# design.net
KiCad netlist of a schematic drawn in EasyEDA
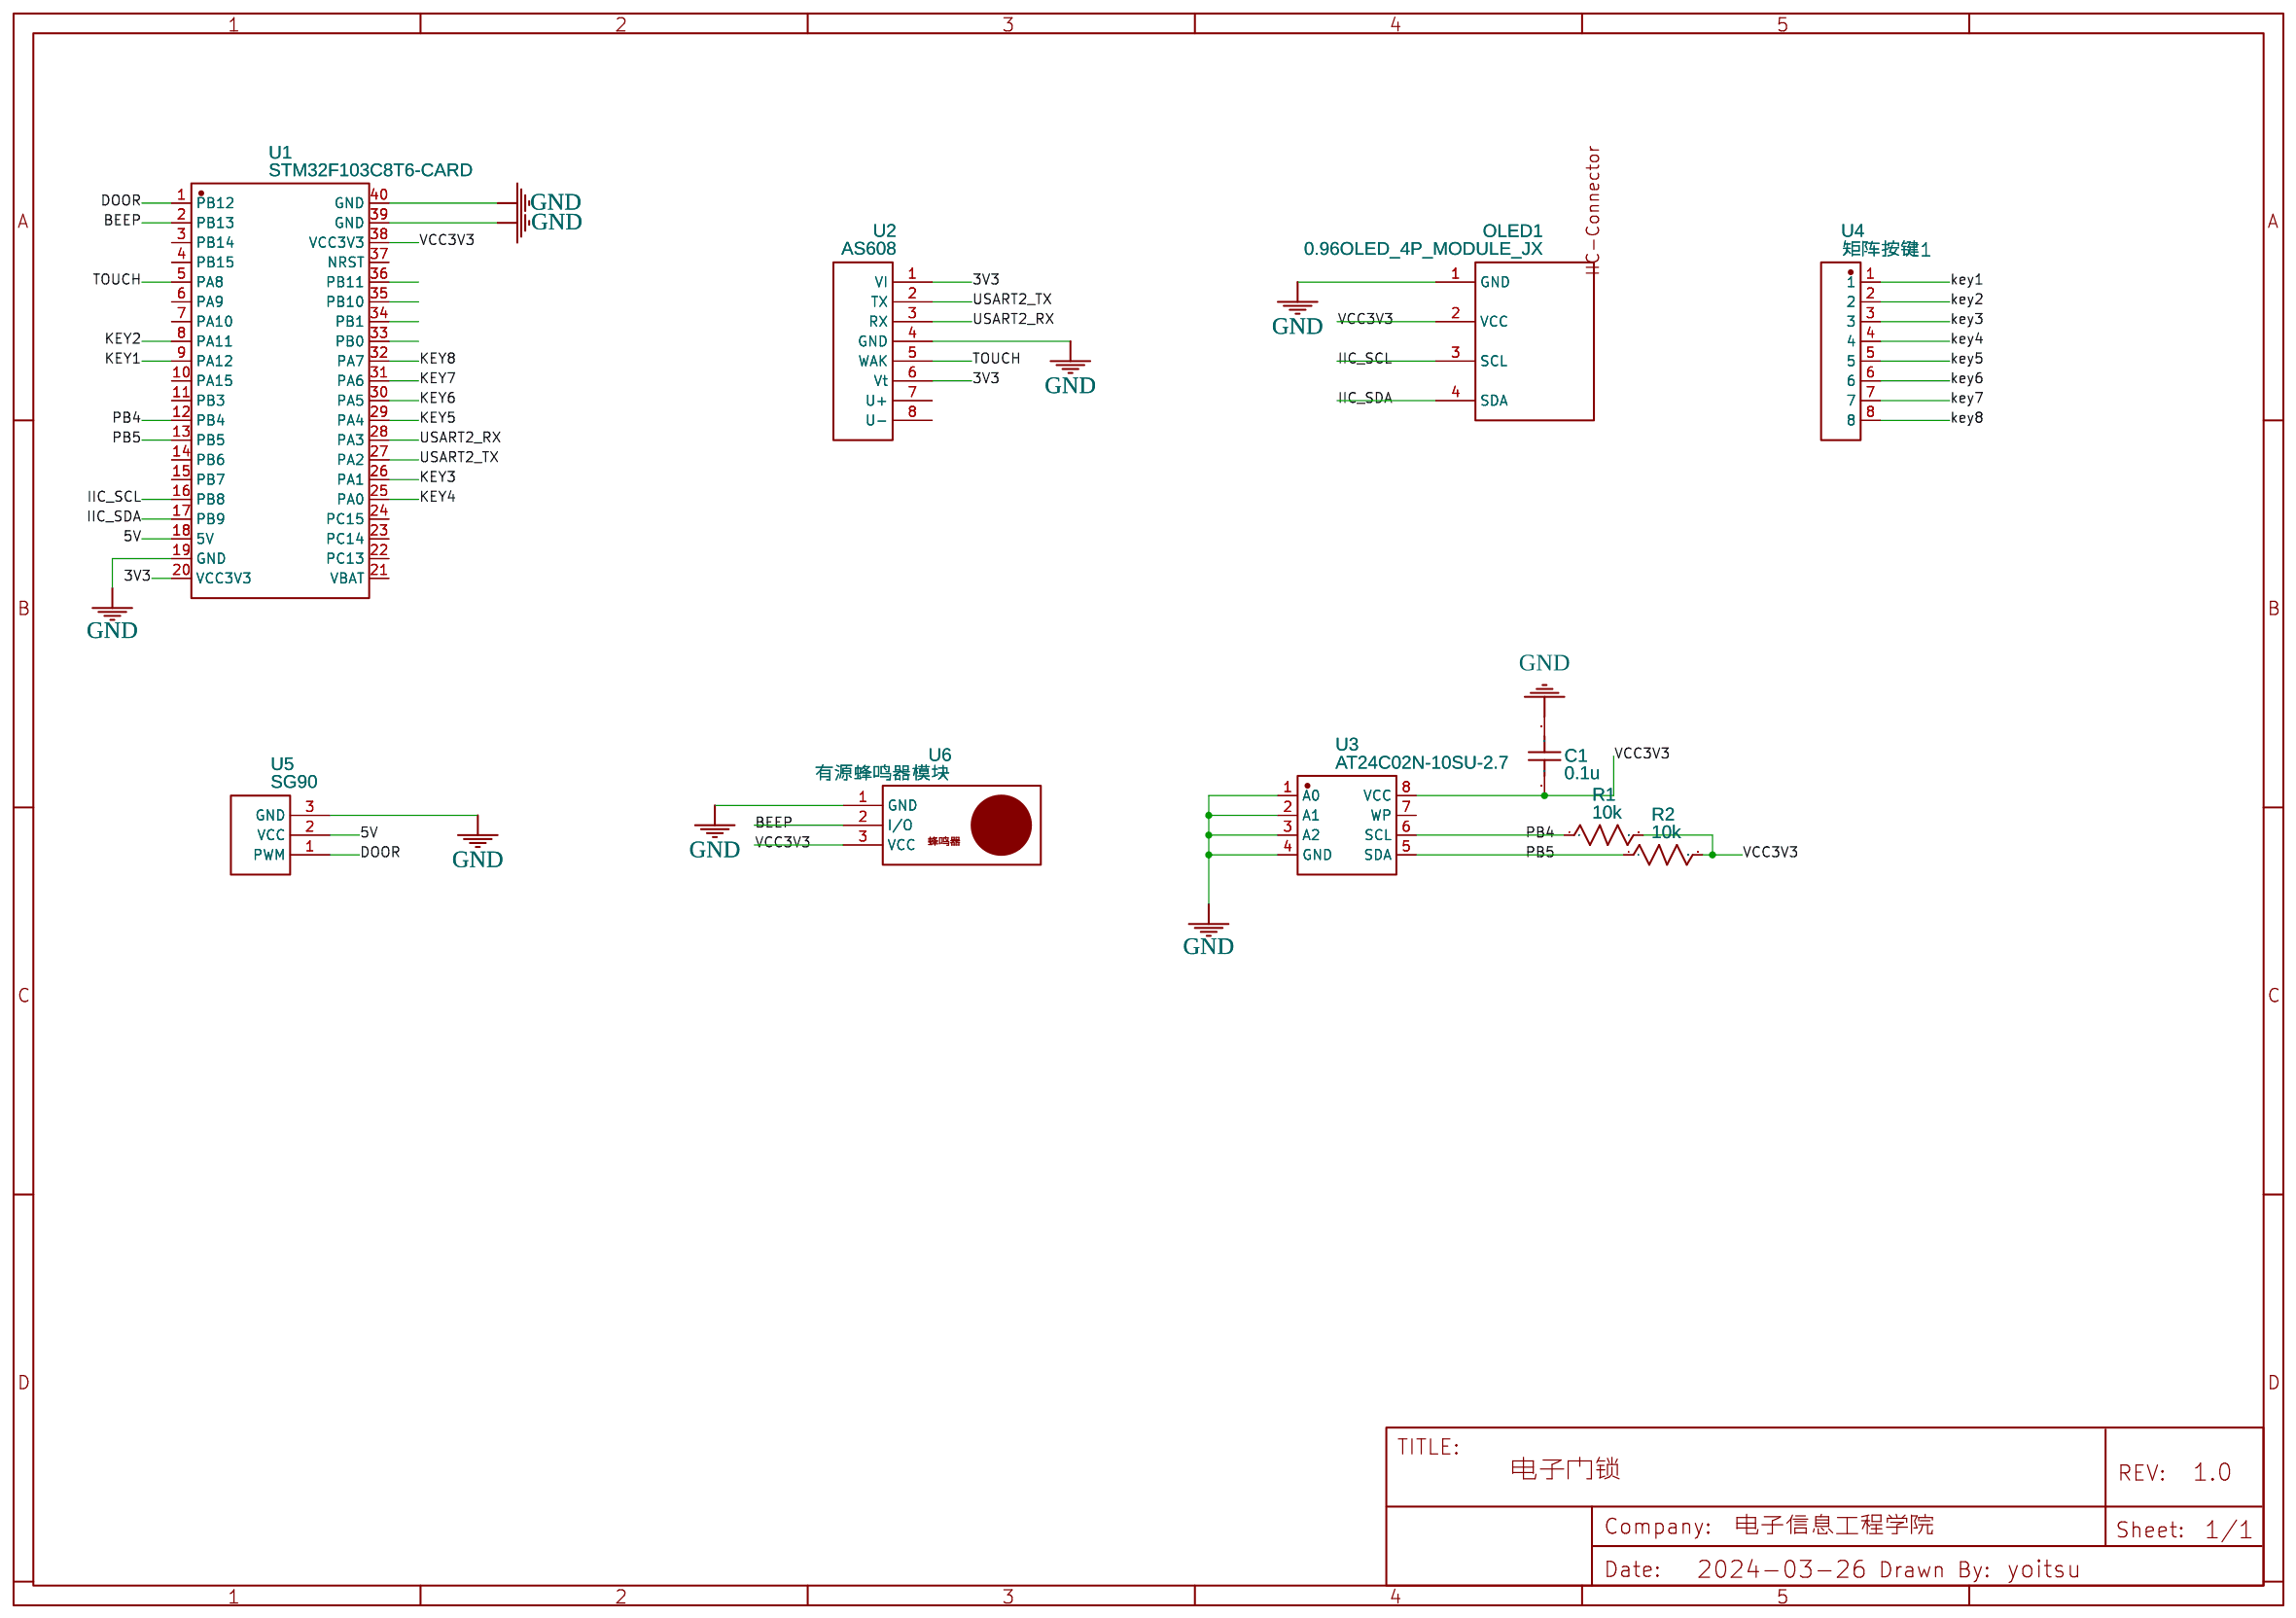
[diagram p0: schematic sheet]

(export (version "E")
  (design (tool "Eeschema 10.0.6"))
  (components
    (comp (ref "C1") (value "0.1u") (libsource (lib "") (part "C_0603_US")))
    (comp (ref "OLED1") (value "0.96OLED_4P_MODULE_JX") (libsource (lib "") (part "0.96OLED_4P_MODULE_JX")))
    (comp (ref "R1") (value "10k") (libsource (lib "") (part "R_0805_US")))
    (comp (ref "R2") (value "10k") (libsource (lib "") (part "R_0805_US")))
    (comp (ref "U1")
      (value "STM32F103C8T6-CARD")
      (fields (field (name "Manufacturer Part") "STM32F103C8T6-Card"))
      (libsource (lib "") (part "STM32F103C8T6-CARD"))
    )
    (comp (ref "U2")
      (value "AS608")
      (fields (field (name "Manufacturer") "lengyuefeng") (field (name "Supplier") "lengyuefeng"))
      (libsource (lib "") (part "AS608"))
    )
    (comp (ref "U3") (value "AT24C02N-10SU-2.7") (libsource (lib "") (part "AT24C02N-10SU-2.7")))
    (comp (ref "U4")
      (value "矩阵按键1")
      (fields
        (field (name "Manufacturer Part") "KH-2.54FH-1X8P-H8.5")
        (field (name "Manufacturer") "kinghelm(金航标)")
      )
      (libsource (lib "") (part "KH-2.54FH-1X8P-H8.5"))
    )
    (comp (ref "U5") (value "SG90") (libsource (lib "") (part "SG90")))
    (comp (ref "U6") (value "有源蜂鸣器模块") (libsource (lib "") (part "有源蜂鸣器模块")))
  )
  (nets
    (net (code "1") (name "/3V3") (class "Default")
      (node (ref "U1") (pin "20") (pinfunction "VCC3V3_20") (pintype "unspecified"))
      (node (ref "U2") (pin "1") (pinfunction "VI_1") (pintype "unspecified"))
      (node (ref "U2") (pin "6") (pinfunction "Vt_6") (pintype "unspecified"))
    )
    (net (code "2") (name "/5V") (class "Default")
      (node (ref "U1") (pin "18") (pinfunction "5V_18") (pintype "unspecified"))
      (node (ref "U5") (pin "2") (pinfunction "VCC_2") (pintype "unspecified"))
    )
    (net (code "3") (name "/BEEP") (class "Default")
      (node (ref "U1") (pin "2") (pinfunction "PB13_2") (pintype "unspecified"))
      (node (ref "U6") (pin "2") (pinfunction "I/O_2") (pintype "unspecified"))
    )
    (net (code "4") (name "/DOOR") (class "Default")
      (node (ref "U1") (pin "1") (pinfunction "PB12_1") (pintype "unspecified"))
      (node (ref "U5") (pin "1") (pinfunction "PWM_1") (pintype "unspecified"))
    )
    (net (code "5") (name "/IIC_SCL") (class "Default")
      (node (ref "OLED1") (pin "3") (pinfunction "SCL_3") (pintype "unspecified"))
      (node (ref "U1") (pin "16") (pinfunction "PB8_16") (pintype "unspecified"))
    )
    (net (code "6") (name "/IIC_SDA") (class "Default")
      (node (ref "OLED1") (pin "4") (pinfunction "SDA_4") (pintype "unspecified"))
      (node (ref "U1") (pin "17") (pinfunction "PB9_17") (pintype "unspecified"))
    )
    (net (code "7") (name "/KEY1") (class "Default")
      (node (ref "U1") (pin "9") (pinfunction "PA12_9") (pintype "unspecified"))
    )
    (net (code "8") (name "/KEY2") (class "Default")
      (node (ref "U1") (pin "8") (pinfunction "PA11_8") (pintype "unspecified"))
    )
    (net (code "9") (name "/KEY3") (class "Default")
      (node (ref "U1") (pin "26") (pinfunction "PA1_26") (pintype "unspecified"))
    )
    (net (code "10") (name "/KEY4") (class "Default")
      (node (ref "U1") (pin "25") (pinfunction "PA0_25") (pintype "unspecified"))
    )
    (net (code "11") (name "/KEY5") (class "Default")
      (node (ref "U1") (pin "29") (pinfunction "PA4_29") (pintype "unspecified"))
    )
    (net (code "12") (name "/KEY6") (class "Default")
      (node (ref "U1") (pin "30") (pinfunction "PA5_30") (pintype "unspecified"))
    )
    (net (code "13") (name "/KEY7") (class "Default")
      (node (ref "U1") (pin "31") (pinfunction "PA6_31") (pintype "unspecified"))
    )
    (net (code "14") (name "/KEY8") (class "Default")
      (node (ref "U1") (pin "32") (pinfunction "PA7_32") (pintype "unspecified"))
    )
    (net (code "15") (name "/PB4") (class "Default")
      (node (ref "R1") (pin "1") (pinfunction "1_1") (pintype "unspecified"))
      (node (ref "U1") (pin "12") (pinfunction "PB4_12") (pintype "unspecified"))
      (node (ref "U3") (pin "6") (pinfunction "SCL_6") (pintype "unspecified"))
    )
    (net (code "16") (name "/PB5") (class "Default")
      (node (ref "R2") (pin "1") (pinfunction "1_1") (pintype "unspecified"))
      (node (ref "U1") (pin "13") (pinfunction "PB5_13") (pintype "unspecified"))
      (node (ref "U3") (pin "5") (pinfunction "SDA_5") (pintype "unspecified"))
    )
    (net (code "17") (name "/TOUCH") (class "Default")
      (node (ref "U1") (pin "5") (pinfunction "PA8_5") (pintype "unspecified"))
      (node (ref "U2") (pin "5") (pinfunction "WAK_5") (pintype "unspecified"))
    )
    (net (code "18") (name "/USART2_RX") (class "Default")
      (node (ref "U1") (pin "28") (pinfunction "PA3_28") (pintype "unspecified"))
      (node (ref "U2") (pin "3") (pinfunction "RX_3") (pintype "unspecified"))
    )
    (net (code "19") (name "/USART2_TX") (class "Default")
      (node (ref "U1") (pin "27") (pinfunction "PA2_27") (pintype "unspecified"))
      (node (ref "U2") (pin "2") (pinfunction "TX_2") (pintype "unspecified"))
    )
    (net (code "20") (name "/VCC3V3") (class "Default")
      (node (ref "C1") (pin "1") (pinfunction "1_1") (pintype "unspecified"))
      (node (ref "OLED1") (pin "2") (pinfunction "VCC_2") (pintype "unspecified"))
      (node (ref "R1") (pin "2") (pinfunction "2_2") (pintype "unspecified"))
      (node (ref "R2") (pin "2") (pinfunction "2_2") (pintype "unspecified"))
      (node (ref "U1") (pin "38") (pinfunction "VCC3V3_38") (pintype "unspecified"))
      (node (ref "U3") (pin "8") (pinfunction "VCC_8") (pintype "unspecified"))
      (node (ref "U6") (pin "3") (pinfunction "VCC_3") (pintype "unspecified"))
    )
    (net (code "21") (name "/key1") (class "Default")
      (node (ref "U4") (pin "1") (pinfunction "1_1") (pintype "unspecified"))
    )
    (net (code "22") (name "/key2") (class "Default")
      (node (ref "U4") (pin "2") (pinfunction "2_2") (pintype "unspecified"))
    )
    (net (code "23") (name "/key3") (class "Default")
      (node (ref "U4") (pin "3") (pinfunction "3_3") (pintype "unspecified"))
    )
    (net (code "24") (name "/key4") (class "Default")
      (node (ref "U4") (pin "4") (pinfunction "4_4") (pintype "unspecified"))
    )
    (net (code "25") (name "/key5") (class "Default")
      (node (ref "U4") (pin "5") (pinfunction "5_5") (pintype "unspecified"))
    )
    (net (code "26") (name "/key6") (class "Default")
      (node (ref "U4") (pin "6") (pinfunction "6_6") (pintype "unspecified"))
    )
    (net (code "27") (name "/key7") (class "Default")
      (node (ref "U4") (pin "7") (pinfunction "7_7") (pintype "unspecified"))
    )
    (net (code "28") (name "/key8") (class "Default")
      (node (ref "U4") (pin "8") (pinfunction "8_8") (pintype "unspecified"))
    )
    (net (code "29") (name "GND") (class "Default")
      (node (ref "C1") (pin "2") (pinfunction "2_2") (pintype "unspecified"))
      (node (ref "OLED1") (pin "1") (pinfunction "GND_1") (pintype "unspecified"))
      (node (ref "U1") (pin "19") (pinfunction "GND_19") (pintype "unspecified"))
      (node (ref "U1") (pin "39") (pinfunction "GND_39") (pintype "unspecified"))
      (node (ref "U1") (pin "40") (pinfunction "GND_40") (pintype "unspecified"))
      (node (ref "U2") (pin "4") (pinfunction "GND_4") (pintype "unspecified"))
      (node (ref "U3") (pin "1") (pinfunction "A0_1") (pintype "unspecified"))
      (node (ref "U3") (pin "2") (pinfunction "A1_2") (pintype "unspecified"))
      (node (ref "U3") (pin "3") (pinfunction "A2_3") (pintype "unspecified"))
      (node (ref "U3") (pin "4") (pinfunction "GND_4") (pintype "unspecified"))
      (node (ref "U5") (pin "3") (pinfunction "GND_3") (pintype "unspecified"))
      (node (ref "U6") (pin "1") (pinfunction "GND_1") (pintype "unspecified"))
    )
    (net (code "30") (name "unconnected-(U1-NRST-Pad37)") (class "Default")
      (node (ref "U1") (pin "37") (pinfunction "NRST_37") (pintype "unspecified"))
    )
    (net (code "31") (name "unconnected-(U1-PA9-Pad6)") (class "Default")
      (node (ref "U1") (pin "6") (pinfunction "PA9_6") (pintype "unspecified"))
    )
    (net (code "32") (name "unconnected-(U1-PA10-Pad7)") (class "Default")
      (node (ref "U1") (pin "7") (pinfunction "PA10_7") (pintype "unspecified"))
    )
    (net (code "33") (name "unconnected-(U1-PA15-Pad10)") (class "Default")
      (node (ref "U1") (pin "10") (pinfunction "PA15_10") (pintype "unspecified"))
    )
    (net (code "34") (name "unconnected-(U1-PB0-Pad33)") (class "Default")
      (node (ref "U1") (pin "33") (pinfunction "PB0_33") (pintype "unspecified"))
    )
    (net (code "35") (name "unconnected-(U1-PB1-Pad34)") (class "Default")
      (node (ref "U1") (pin "34") (pinfunction "PB1_34") (pintype "unspecified"))
    )
    (net (code "36") (name "unconnected-(U1-PB3-Pad11)") (class "Default")
      (node (ref "U1") (pin "11") (pinfunction "PB3_11") (pintype "unspecified"))
    )
    (net (code "37") (name "unconnected-(U1-PB6-Pad14)") (class "Default")
      (node (ref "U1") (pin "14") (pinfunction "PB6_14") (pintype "unspecified"))
    )
    (net (code "38") (name "unconnected-(U1-PB7-Pad15)") (class "Default")
      (node (ref "U1") (pin "15") (pinfunction "PB7_15") (pintype "unspecified"))
    )
    (net (code "39") (name "unconnected-(U1-PB10-Pad35)") (class "Default")
      (node (ref "U1") (pin "35") (pinfunction "PB10_35") (pintype "unspecified"))
    )
    (net (code "40") (name "unconnected-(U1-PB11-Pad36)") (class "Default")
      (node (ref "U1") (pin "36") (pinfunction "PB11_36") (pintype "unspecified"))
    )
    (net (code "41") (name "unconnected-(U1-PB14-Pad3)") (class "Default")
      (node (ref "U1") (pin "3") (pinfunction "PB14_3") (pintype "unspecified"))
    )
    (net (code "42") (name "unconnected-(U1-PB15-Pad4)") (class "Default")
      (node (ref "U1") (pin "4") (pinfunction "PB15_4") (pintype "unspecified"))
    )
    (net (code "43") (name "unconnected-(U1-PC13-Pad22)") (class "Default")
      (node (ref "U1") (pin "22") (pinfunction "PC13_22") (pintype "unspecified"))
    )
    (net (code "44") (name "unconnected-(U1-PC14-Pad23)") (class "Default")
      (node (ref "U1") (pin "23") (pinfunction "PC14_23") (pintype "unspecified"))
    )
    (net (code "45") (name "unconnected-(U1-PC15-Pad24)") (class "Default")
      (node (ref "U1") (pin "24") (pinfunction "PC15_24") (pintype "unspecified"))
    )
    (net (code "46") (name "unconnected-(U1-VBAT-Pad21)") (class "Default")
      (node (ref "U1") (pin "21") (pinfunction "VBAT_21") (pintype "unspecified"))
    )
    (net (code "47") (name "unconnected-(U2-U+-Pad7)") (class "Default")
      (node (ref "U2") (pin "7") (pinfunction "U+_7") (pintype "unspecified"))
    )
    (net (code "48") (name "unconnected-(U2-U--Pad8)") (class "Default")
      (node (ref "U2") (pin "8") (pinfunction "U-_8") (pintype "unspecified"))
    )
    (net (code "49") (name "unconnected-(U3-WP-Pad7)") (class "Default")
      (node (ref "U3") (pin "7") (pinfunction "WP_7") (pintype "unspecified"))
    )
  )
)
